# MultiSensor_MPL_TCA_0805.net
KiCad netlist of a schematic drawn in EAGLE
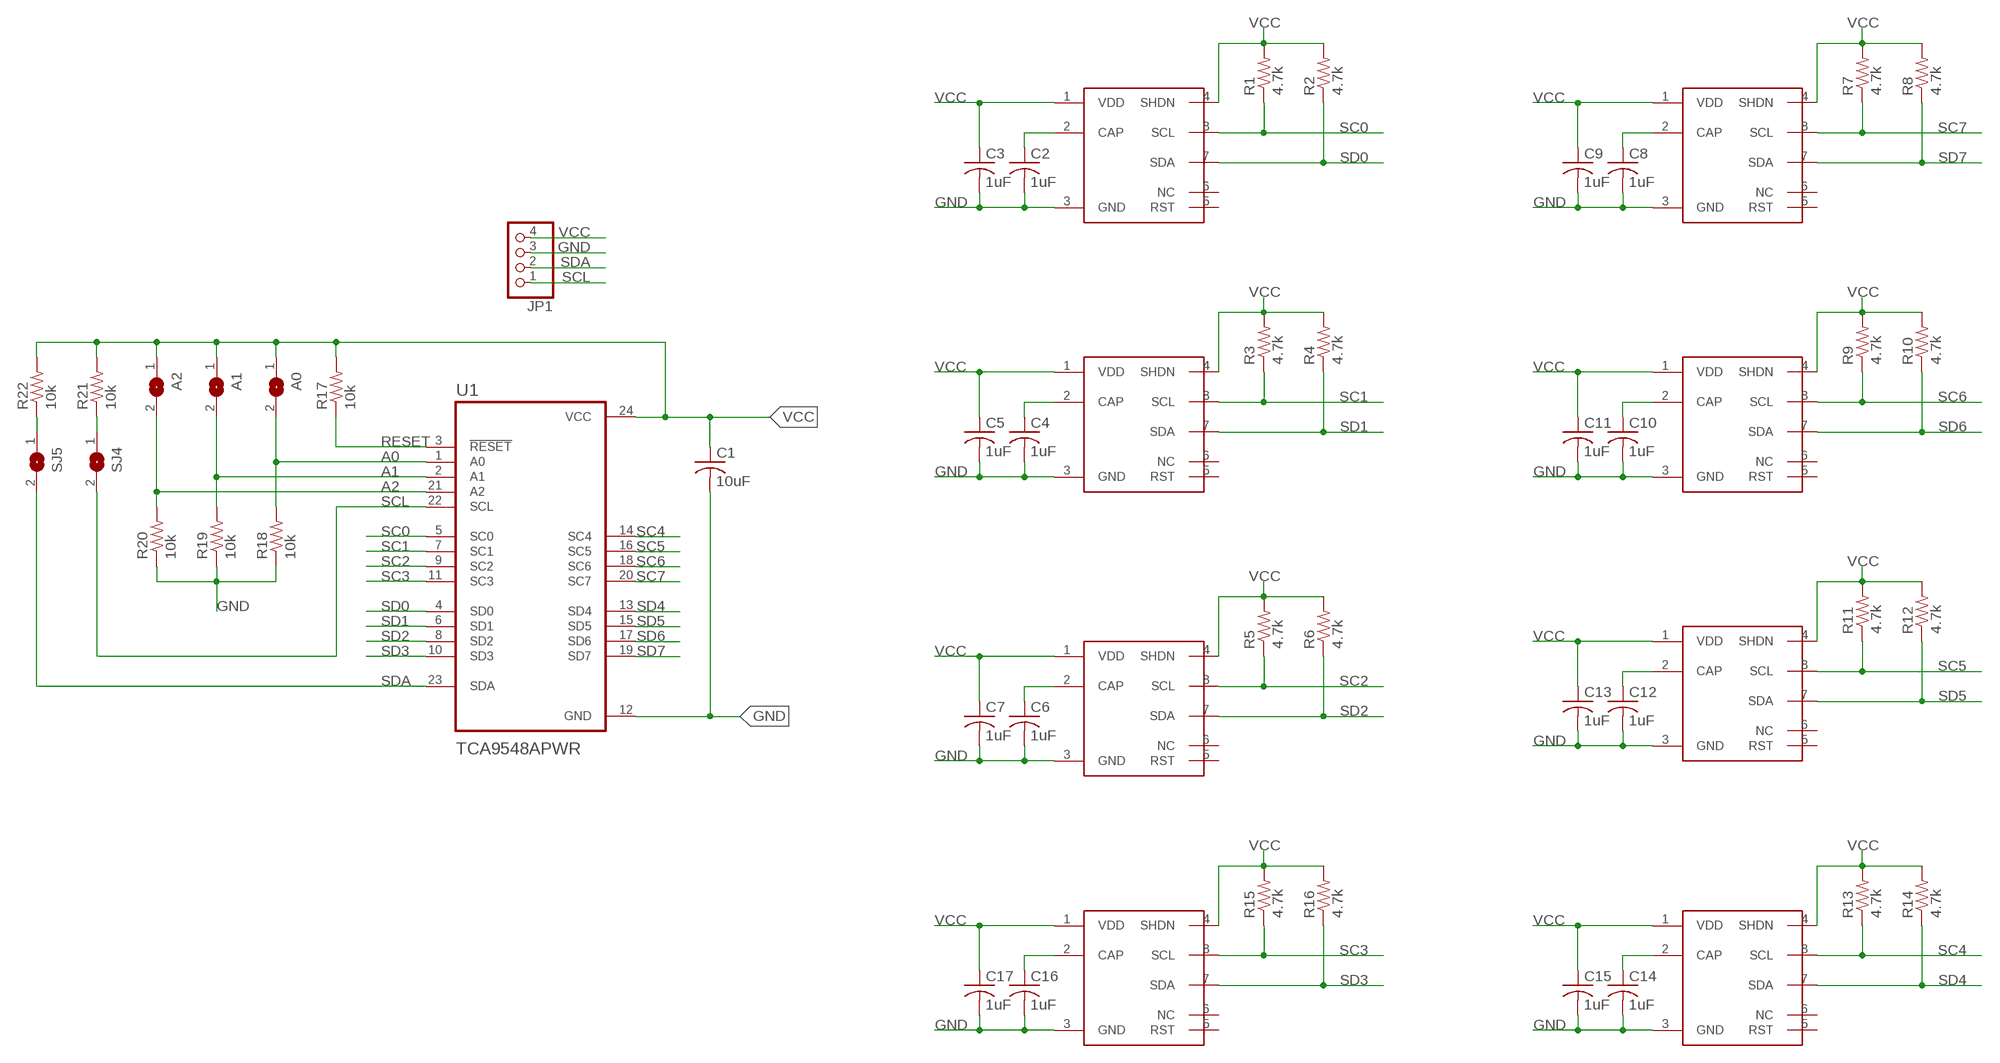
[diagram p0: schematic, sheet 1]

(export (version "E")
  (design (tool "Eeschema 10.0.6"))
  (components
    (comp (ref "A0") (value "SJ") (footprint "eagle-import:SJ") (libsource (lib "eagle-import") (part "SJ")))
    (comp (ref "A1") (value "SJ") (footprint "eagle-import:SJ") (libsource (lib "eagle-import") (part "SJ")))
    (comp (ref "A2") (value "SJ") (footprint "eagle-import:SJ") (libsource (lib "eagle-import") (part "SJ")))
    (comp (ref "B1")
      (value "MPL115A2T1")
      (footprint "eagle-import:MPL115A2T1")
      (libsource (lib "eagle-import") (part "MPL115A2T1"))
    )
    (comp (ref "B2")
      (value "MPL115A2T1")
      (footprint "eagle-import:MPL115A2T1")
      (libsource (lib "eagle-import") (part "MPL115A2T1"))
    )
    (comp (ref "B3")
      (value "MPL115A2T1")
      (footprint "eagle-import:MPL115A2T1")
      (libsource (lib "eagle-import") (part "MPL115A2T1"))
    )
    (comp (ref "B4")
      (value "MPL115A2T1")
      (footprint "eagle-import:MPL115A2T1")
      (libsource (lib "eagle-import") (part "MPL115A2T1"))
    )
    (comp (ref "B5")
      (value "MPL115A2T1")
      (footprint "eagle-import:MPL115A2T1")
      (libsource (lib "eagle-import") (part "MPL115A2T1"))
    )
    (comp (ref "B6")
      (value "MPL115A2T1")
      (footprint "eagle-import:MPL115A2T1")
      (libsource (lib "eagle-import") (part "MPL115A2T1"))
    )
    (comp (ref "B7")
      (value "MPL115A2T1")
      (footprint "eagle-import:MPL115A2T1")
      (libsource (lib "eagle-import") (part "MPL115A2T1"))
    )
    (comp (ref "B8")
      (value "MPL115A2T1")
      (footprint "eagle-import:MPL115A2T1")
      (libsource (lib "eagle-import") (part "MPL115A2T1"))
    )
    (comp (ref "C1")
      (value "10uF")
      (footprint "eagle-import:C1206")
      (libsource (lib "eagle-import") (part "C-USC1206"))
    )
    (comp (ref "C2")
      (value "1uF")
      (footprint "eagle-import:C0805")
      (libsource (lib "eagle-import") (part "C-USC0805"))
    )
    (comp (ref "C3")
      (value "1uF")
      (footprint "eagle-import:C0805")
      (libsource (lib "eagle-import") (part "C-USC0805"))
    )
    (comp (ref "C4")
      (value "1uF")
      (footprint "eagle-import:C0805")
      (libsource (lib "eagle-import") (part "C-USC0805"))
    )
    (comp (ref "C5")
      (value "1uF")
      (footprint "eagle-import:C0805")
      (libsource (lib "eagle-import") (part "C-USC0805"))
    )
    (comp (ref "C6")
      (value "1uF")
      (footprint "eagle-import:C0805")
      (libsource (lib "eagle-import") (part "C-USC0805"))
    )
    (comp (ref "C7")
      (value "1uF")
      (footprint "eagle-import:C0805")
      (libsource (lib "eagle-import") (part "C-USC0805"))
    )
    (comp (ref "C8")
      (value "1uF")
      (footprint "eagle-import:C0805")
      (libsource (lib "eagle-import") (part "C-USC0805"))
    )
    (comp (ref "C9")
      (value "1uF")
      (footprint "eagle-import:C0805")
      (libsource (lib "eagle-import") (part "C-USC0805"))
    )
    (comp (ref "C10")
      (value "1uF")
      (footprint "eagle-import:C0805")
      (libsource (lib "eagle-import") (part "C-USC0805"))
    )
    (comp (ref "C11")
      (value "1uF")
      (footprint "eagle-import:C0805")
      (libsource (lib "eagle-import") (part "C-USC0805"))
    )
    (comp (ref "C12")
      (value "1uF")
      (footprint "eagle-import:C0805")
      (libsource (lib "eagle-import") (part "C-USC0805"))
    )
    (comp (ref "C13")
      (value "1uF")
      (footprint "eagle-import:C0805")
      (libsource (lib "eagle-import") (part "C-USC0805"))
    )
    (comp (ref "C14")
      (value "1uF")
      (footprint "eagle-import:C0805")
      (libsource (lib "eagle-import") (part "C-USC0805"))
    )
    (comp (ref "C15")
      (value "1uF")
      (footprint "eagle-import:C0805")
      (libsource (lib "eagle-import") (part "C-USC0805"))
    )
    (comp (ref "C16")
      (value "1uF")
      (footprint "eagle-import:C0805")
      (libsource (lib "eagle-import") (part "C-USC0805"))
    )
    (comp (ref "C17")
      (value "1uF")
      (footprint "eagle-import:C0805")
      (libsource (lib "eagle-import") (part "C-USC0805"))
    )
    (comp (ref "JP1")
      (value "PINHD-1X4")
      (footprint "eagle-import:1X04")
      (libsource (lib "eagle-import") (part "PINHD-1X4"))
    )
    (comp (ref "R1")
      (value "4.7k")
      (footprint "eagle-import:R0805")
      (libsource (lib "eagle-import") (part "R-US_R0805"))
    )
    (comp (ref "R2")
      (value "4.7k")
      (footprint "eagle-import:R0805")
      (libsource (lib "eagle-import") (part "R-US_R0805"))
    )
    (comp (ref "R3")
      (value "4.7k")
      (footprint "eagle-import:R0805")
      (libsource (lib "eagle-import") (part "R-US_R0805"))
    )
    (comp (ref "R4")
      (value "4.7k")
      (footprint "eagle-import:R0805")
      (libsource (lib "eagle-import") (part "R-US_R0805"))
    )
    (comp (ref "R5")
      (value "4.7k")
      (footprint "eagle-import:R0805")
      (libsource (lib "eagle-import") (part "R-US_R0805"))
    )
    (comp (ref "R6")
      (value "4.7k")
      (footprint "eagle-import:R0805")
      (libsource (lib "eagle-import") (part "R-US_R0805"))
    )
    (comp (ref "R7")
      (value "4.7k")
      (footprint "eagle-import:R0805")
      (libsource (lib "eagle-import") (part "R-US_R0805"))
    )
    (comp (ref "R8")
      (value "4.7k")
      (footprint "eagle-import:R0805")
      (libsource (lib "eagle-import") (part "R-US_R0805"))
    )
    (comp (ref "R9")
      (value "4.7k")
      (footprint "eagle-import:R0805")
      (libsource (lib "eagle-import") (part "R-US_R0805"))
    )
    (comp (ref "R10")
      (value "4.7k")
      (footprint "eagle-import:R0805")
      (libsource (lib "eagle-import") (part "R-US_R0805"))
    )
    (comp (ref "R11")
      (value "4.7k")
      (footprint "eagle-import:R0805")
      (libsource (lib "eagle-import") (part "R-US_R0805"))
    )
    (comp (ref "R12")
      (value "4.7k")
      (footprint "eagle-import:R0805")
      (libsource (lib "eagle-import") (part "R-US_R0805"))
    )
    (comp (ref "R13")
      (value "4.7k")
      (footprint "eagle-import:R0805")
      (libsource (lib "eagle-import") (part "R-US_R0805"))
    )
    (comp (ref "R14")
      (value "4.7k")
      (footprint "eagle-import:R0805")
      (libsource (lib "eagle-import") (part "R-US_R0805"))
    )
    (comp (ref "R15")
      (value "4.7k")
      (footprint "eagle-import:R0805")
      (libsource (lib "eagle-import") (part "R-US_R0805"))
    )
    (comp (ref "R16")
      (value "4.7k")
      (footprint "eagle-import:R0805")
      (libsource (lib "eagle-import") (part "R-US_R0805"))
    )
    (comp (ref "R17")
      (value "10k")
      (footprint "eagle-import:R0805")
      (libsource (lib "eagle-import") (part "resistor_348_R-US_R0805"))
    )
    (comp (ref "R18")
      (value "10k")
      (footprint "eagle-import:R0805")
      (libsource (lib "eagle-import") (part "resistor_348_R-US_R0805"))
    )
    (comp (ref "R19")
      (value "10k")
      (footprint "eagle-import:R0805")
      (libsource (lib "eagle-import") (part "resistor_348_R-US_R0805"))
    )
    (comp (ref "R20")
      (value "10k")
      (footprint "eagle-import:R0805")
      (libsource (lib "eagle-import") (part "resistor_348_R-US_R0805"))
    )
    (comp (ref "R21")
      (value "10k")
      (footprint "eagle-import:R0805")
      (libsource (lib "eagle-import") (part "resistor_348_R-US_R0805"))
    )
    (comp (ref "R22")
      (value "10k")
      (footprint "eagle-import:R0805")
      (libsource (lib "eagle-import") (part "resistor_348_R-US_R0805"))
    )
    (comp (ref "SJ4") (value "SJ") (footprint "eagle-import:SJ") (libsource (lib "eagle-import") (part "SJ")))
    (comp (ref "SJ5") (value "SJ") (footprint "eagle-import:SJ") (libsource (lib "eagle-import") (part "SJ")))
    (comp (ref "U1")
      (value "TCA9548APWR")
      (footprint "eagle-import:SOP65P640X120-24N")
      (fields (field (name "DIGI-KEY_PART_NUMBER") "296-34905-1-ND") (field (name "MF") "Texas Instruments"))
      (libsource (lib "eagle-import") (part "TCA9548APWR"))
    )
  )
  (nets
    (net (code "1") (name "/A0") (class "Default")
      (node (ref "A0") (pin "2") (pinfunction "2_2") (pintype "passive"))
      (node (ref "R18") (pin "2") (pinfunction "2_2") (pintype "passive"))
      (node (ref "U1") (pin "1") (pinfunction "A0_1") (pintype "input"))
    )
    (net (code "2") (name "/A1") (class "Default")
      (node (ref "A1") (pin "2") (pinfunction "2_2") (pintype "passive"))
      (node (ref "R19") (pin "2") (pinfunction "2_2") (pintype "passive"))
      (node (ref "U1") (pin "2") (pinfunction "A1_2") (pintype "input"))
    )
    (net (code "3") (name "/A2") (class "Default")
      (node (ref "A2") (pin "2") (pinfunction "2_2") (pintype "passive"))
      (node (ref "R20") (pin "2") (pinfunction "2_2") (pintype "passive"))
      (node (ref "U1") (pin "21") (pinfunction "A2_21") (pintype "input"))
    )
    (net (code "4") (name "/RESET") (class "Default")
      (node (ref "R17") (pin "1") (pinfunction "1_1") (pintype "passive"))
      (node (ref "U1") (pin "3") (pinfunction "~{RESET}_3") (pintype "input"))
    )
    (net (code "5") (name "/SC0") (class "Default")
      (node (ref "B1") (pin "8") (pinfunction "SCL_8") (pintype "bidirectional"))
      (node (ref "R1") (pin "1") (pinfunction "1_1") (pintype "passive"))
      (node (ref "U1") (pin "5") (pinfunction "SC0_5") (pintype "bidirectional"))
    )
    (net (code "6") (name "/SC1") (class "Default")
      (node (ref "B2") (pin "8") (pinfunction "SCL_8") (pintype "bidirectional"))
      (node (ref "R3") (pin "1") (pinfunction "1_1") (pintype "passive"))
      (node (ref "U1") (pin "7") (pinfunction "SC1_7") (pintype "bidirectional"))
    )
    (net (code "7") (name "/SC2") (class "Default")
      (node (ref "B3") (pin "8") (pinfunction "SCL_8") (pintype "bidirectional"))
      (node (ref "R5") (pin "1") (pinfunction "1_1") (pintype "passive"))
      (node (ref "U1") (pin "9") (pinfunction "SC2_9") (pintype "bidirectional"))
    )
    (net (code "8") (name "/SC3") (class "Default")
      (node (ref "B8") (pin "8") (pinfunction "SCL_8") (pintype "bidirectional"))
      (node (ref "R15") (pin "1") (pinfunction "1_1") (pintype "passive"))
      (node (ref "U1") (pin "11") (pinfunction "SC3_11") (pintype "bidirectional"))
    )
    (net (code "9") (name "/SC4") (class "Default")
      (node (ref "B7") (pin "8") (pinfunction "SCL_8") (pintype "bidirectional"))
      (node (ref "R13") (pin "1") (pinfunction "1_1") (pintype "passive"))
      (node (ref "U1") (pin "14") (pinfunction "SC4_14") (pintype "bidirectional"))
    )
    (net (code "10") (name "/SC5") (class "Default")
      (node (ref "B6") (pin "8") (pinfunction "SCL_8") (pintype "bidirectional"))
      (node (ref "R11") (pin "1") (pinfunction "1_1") (pintype "passive"))
      (node (ref "U1") (pin "16") (pinfunction "SC5_16") (pintype "bidirectional"))
    )
    (net (code "11") (name "/SC6") (class "Default")
      (node (ref "B5") (pin "8") (pinfunction "SCL_8") (pintype "bidirectional"))
      (node (ref "R9") (pin "1") (pinfunction "1_1") (pintype "passive"))
      (node (ref "U1") (pin "18") (pinfunction "SC6_18") (pintype "bidirectional"))
    )
    (net (code "12") (name "/SC7") (class "Default")
      (node (ref "B4") (pin "8") (pinfunction "SCL_8") (pintype "bidirectional"))
      (node (ref "R7") (pin "1") (pinfunction "1_1") (pintype "passive"))
      (node (ref "U1") (pin "20") (pinfunction "SC7_20") (pintype "bidirectional"))
    )
    (net (code "13") (name "/SCL") (class "Default")
      (node (ref "JP1") (pin "1") (pinfunction "1_1") (pintype "passive"))
      (node (ref "SJ4") (pin "2") (pinfunction "2_2") (pintype "passive"))
      (node (ref "U1") (pin "22") (pinfunction "SCL_22") (pintype "input"))
    )
    (net (code "14") (name "/SD0") (class "Default")
      (node (ref "B1") (pin "7") (pinfunction "SDA_7") (pintype "bidirectional"))
      (node (ref "R2") (pin "1") (pinfunction "1_1") (pintype "passive"))
      (node (ref "U1") (pin "4") (pinfunction "SD0_4") (pintype "bidirectional"))
    )
    (net (code "15") (name "/SD1") (class "Default")
      (node (ref "B2") (pin "7") (pinfunction "SDA_7") (pintype "bidirectional"))
      (node (ref "R4") (pin "1") (pinfunction "1_1") (pintype "passive"))
      (node (ref "U1") (pin "6") (pinfunction "SD1_6") (pintype "bidirectional"))
    )
    (net (code "16") (name "/SD2") (class "Default")
      (node (ref "B3") (pin "7") (pinfunction "SDA_7") (pintype "bidirectional"))
      (node (ref "R6") (pin "1") (pinfunction "1_1") (pintype "passive"))
      (node (ref "U1") (pin "8") (pinfunction "SD2_8") (pintype "bidirectional"))
    )
    (net (code "17") (name "/SD3") (class "Default")
      (node (ref "B8") (pin "7") (pinfunction "SDA_7") (pintype "bidirectional"))
      (node (ref "R16") (pin "1") (pinfunction "1_1") (pintype "passive"))
      (node (ref "U1") (pin "10") (pinfunction "SD3_10") (pintype "bidirectional"))
    )
    (net (code "18") (name "/SD4") (class "Default")
      (node (ref "B7") (pin "7") (pinfunction "SDA_7") (pintype "bidirectional"))
      (node (ref "R14") (pin "1") (pinfunction "1_1") (pintype "passive"))
      (node (ref "U1") (pin "13") (pinfunction "SD4_13") (pintype "bidirectional"))
    )
    (net (code "19") (name "/SD5") (class "Default")
      (node (ref "B6") (pin "7") (pinfunction "SDA_7") (pintype "bidirectional"))
      (node (ref "R12") (pin "1") (pinfunction "1_1") (pintype "passive"))
      (node (ref "U1") (pin "15") (pinfunction "SD5_15") (pintype "bidirectional"))
    )
    (net (code "20") (name "/SD6") (class "Default")
      (node (ref "B5") (pin "7") (pinfunction "SDA_7") (pintype "bidirectional"))
      (node (ref "R10") (pin "1") (pinfunction "1_1") (pintype "passive"))
      (node (ref "U1") (pin "17") (pinfunction "SD6_17") (pintype "bidirectional"))
    )
    (net (code "21") (name "/SD7") (class "Default")
      (node (ref "B4") (pin "7") (pinfunction "SDA_7") (pintype "bidirectional"))
      (node (ref "R8") (pin "1") (pinfunction "1_1") (pintype "passive"))
      (node (ref "U1") (pin "19") (pinfunction "SD7_19") (pintype "bidirectional"))
    )
    (net (code "22") (name "/SDA") (class "Default")
      (node (ref "JP1") (pin "2") (pinfunction "2_2") (pintype "passive"))
      (node (ref "SJ5") (pin "2") (pinfunction "2_2") (pintype "passive"))
      (node (ref "U1") (pin "23") (pinfunction "SDA_23") (pintype "bidirectional"))
    )
    (net (code "23") (name "GND") (class "Default")
      (node (ref "B1") (pin "3") (pinfunction "GND_3") (pintype "bidirectional"))
      (node (ref "B2") (pin "3") (pinfunction "GND_3") (pintype "bidirectional"))
      (node (ref "B3") (pin "3") (pinfunction "GND_3") (pintype "bidirectional"))
      (node (ref "B4") (pin "3") (pinfunction "GND_3") (pintype "bidirectional"))
      (node (ref "B5") (pin "3") (pinfunction "GND_3") (pintype "bidirectional"))
      (node (ref "B6") (pin "3") (pinfunction "GND_3") (pintype "bidirectional"))
      (node (ref "B7") (pin "3") (pinfunction "GND_3") (pintype "bidirectional"))
      (node (ref "B8") (pin "3") (pinfunction "GND_3") (pintype "bidirectional"))
      (node (ref "C1") (pin "2") (pinfunction "2_2") (pintype "passive"))
      (node (ref "C10") (pin "2") (pinfunction "2_2") (pintype "passive"))
      (node (ref "C11") (pin "2") (pinfunction "2_2") (pintype "passive"))
      (node (ref "C12") (pin "2") (pinfunction "2_2") (pintype "passive"))
      (node (ref "C13") (pin "2") (pinfunction "2_2") (pintype "passive"))
      (node (ref "C14") (pin "2") (pinfunction "2_2") (pintype "passive"))
      (node (ref "C15") (pin "2") (pinfunction "2_2") (pintype "passive"))
      (node (ref "C16") (pin "2") (pinfunction "2_2") (pintype "passive"))
      (node (ref "C17") (pin "2") (pinfunction "2_2") (pintype "passive"))
      (node (ref "C2") (pin "2") (pinfunction "2_2") (pintype "passive"))
      (node (ref "C3") (pin "2") (pinfunction "2_2") (pintype "passive"))
      (node (ref "C4") (pin "2") (pinfunction "2_2") (pintype "passive"))
      (node (ref "C5") (pin "2") (pinfunction "2_2") (pintype "passive"))
      (node (ref "C6") (pin "2") (pinfunction "2_2") (pintype "passive"))
      (node (ref "C7") (pin "2") (pinfunction "2_2") (pintype "passive"))
      (node (ref "C8") (pin "2") (pinfunction "2_2") (pintype "passive"))
      (node (ref "C9") (pin "2") (pinfunction "2_2") (pintype "passive"))
      (node (ref "JP1") (pin "3") (pinfunction "3_3") (pintype "passive"))
      (node (ref "R18") (pin "1") (pinfunction "1_1") (pintype "passive"))
      (node (ref "R19") (pin "1") (pinfunction "1_1") (pintype "passive"))
      (node (ref "R20") (pin "1") (pinfunction "1_1") (pintype "passive"))
      (node (ref "U1") (pin "12") (pinfunction "GND_12") (pintype "power_in"))
    )
    (net (code "24") (name "Net-(B1-CAP)") (class "Default")
      (node (ref "B1") (pin "2") (pinfunction "CAP_2") (pintype "bidirectional"))
      (node (ref "C2") (pin "1") (pinfunction "1_1") (pintype "passive"))
    )
    (net (code "25") (name "Net-(B2-CAP)") (class "Default")
      (node (ref "B2") (pin "2") (pinfunction "CAP_2") (pintype "bidirectional"))
      (node (ref "C4") (pin "1") (pinfunction "1_1") (pintype "passive"))
    )
    (net (code "26") (name "Net-(B3-CAP)") (class "Default")
      (node (ref "B3") (pin "2") (pinfunction "CAP_2") (pintype "bidirectional"))
      (node (ref "C6") (pin "1") (pinfunction "1_1") (pintype "passive"))
    )
    (net (code "27") (name "Net-(B4-CAP)") (class "Default")
      (node (ref "B4") (pin "2") (pinfunction "CAP_2") (pintype "bidirectional"))
      (node (ref "C8") (pin "1") (pinfunction "1_1") (pintype "passive"))
    )
    (net (code "28") (name "Net-(B5-CAP)") (class "Default")
      (node (ref "B5") (pin "2") (pinfunction "CAP_2") (pintype "bidirectional"))
      (node (ref "C10") (pin "1") (pinfunction "1_1") (pintype "passive"))
    )
    (net (code "29") (name "Net-(B6-CAP)") (class "Default")
      (node (ref "B6") (pin "2") (pinfunction "CAP_2") (pintype "bidirectional"))
      (node (ref "C12") (pin "1") (pinfunction "1_1") (pintype "passive"))
    )
    (net (code "30") (name "Net-(B7-CAP)") (class "Default")
      (node (ref "B7") (pin "2") (pinfunction "CAP_2") (pintype "bidirectional"))
      (node (ref "C14") (pin "1") (pinfunction "1_1") (pintype "passive"))
    )
    (net (code "31") (name "Net-(B8-CAP)") (class "Default")
      (node (ref "B8") (pin "2") (pinfunction "CAP_2") (pintype "bidirectional"))
      (node (ref "C16") (pin "1") (pinfunction "1_1") (pintype "passive"))
    )
    (net (code "32") (name "Net-(R21-Pad1)") (class "Default")
      (node (ref "R21") (pin "1") (pinfunction "1_1") (pintype "passive"))
      (node (ref "SJ4") (pin "1") (pinfunction "1_1") (pintype "passive"))
    )
    (net (code "33") (name "Net-(R22-Pad1)") (class "Default")
      (node (ref "R22") (pin "1") (pinfunction "1_1") (pintype "passive"))
      (node (ref "SJ5") (pin "1") (pinfunction "1_1") (pintype "passive"))
    )
    (net (code "34") (name "VCC") (class "Default")
      (node (ref "A0") (pin "1") (pinfunction "1_1") (pintype "passive"))
      (node (ref "A1") (pin "1") (pinfunction "1_1") (pintype "passive"))
      (node (ref "A2") (pin "1") (pinfunction "1_1") (pintype "passive"))
      (node (ref "B1") (pin "1") (pinfunction "VDD_1") (pintype "bidirectional"))
      (node (ref "B1") (pin "4") (pinfunction "SHDN_4") (pintype "bidirectional"))
      (node (ref "B2") (pin "1") (pinfunction "VDD_1") (pintype "bidirectional"))
      (node (ref "B2") (pin "4") (pinfunction "SHDN_4") (pintype "bidirectional"))
      (node (ref "B3") (pin "1") (pinfunction "VDD_1") (pintype "bidirectional"))
      (node (ref "B3") (pin "4") (pinfunction "SHDN_4") (pintype "bidirectional"))
      (node (ref "B4") (pin "1") (pinfunction "VDD_1") (pintype "bidirectional"))
      (node (ref "B4") (pin "4") (pinfunction "SHDN_4") (pintype "bidirectional"))
      (node (ref "B5") (pin "1") (pinfunction "VDD_1") (pintype "bidirectional"))
      (node (ref "B5") (pin "4") (pinfunction "SHDN_4") (pintype "bidirectional"))
      (node (ref "B6") (pin "1") (pinfunction "VDD_1") (pintype "bidirectional"))
      (node (ref "B6") (pin "4") (pinfunction "SHDN_4") (pintype "bidirectional"))
      (node (ref "B7") (pin "1") (pinfunction "VDD_1") (pintype "bidirectional"))
      (node (ref "B7") (pin "4") (pinfunction "SHDN_4") (pintype "bidirectional"))
      (node (ref "B8") (pin "1") (pinfunction "VDD_1") (pintype "bidirectional"))
      (node (ref "B8") (pin "4") (pinfunction "SHDN_4") (pintype "bidirectional"))
      (node (ref "C1") (pin "1") (pinfunction "1_1") (pintype "passive"))
      (node (ref "C11") (pin "1") (pinfunction "1_1") (pintype "passive"))
      (node (ref "C13") (pin "1") (pinfunction "1_1") (pintype "passive"))
      (node (ref "C15") (pin "1") (pinfunction "1_1") (pintype "passive"))
      (node (ref "C17") (pin "1") (pinfunction "1_1") (pintype "passive"))
      (node (ref "C3") (pin "1") (pinfunction "1_1") (pintype "passive"))
      (node (ref "C5") (pin "1") (pinfunction "1_1") (pintype "passive"))
      (node (ref "C7") (pin "1") (pinfunction "1_1") (pintype "passive"))
      (node (ref "C9") (pin "1") (pinfunction "1_1") (pintype "passive"))
      (node (ref "JP1") (pin "4") (pinfunction "4_4") (pintype "passive"))
      (node (ref "R1") (pin "2") (pinfunction "2_2") (pintype "passive"))
      (node (ref "R10") (pin "2") (pinfunction "2_2") (pintype "passive"))
      (node (ref "R11") (pin "2") (pinfunction "2_2") (pintype "passive"))
      (node (ref "R12") (pin "2") (pinfunction "2_2") (pintype "passive"))
      (node (ref "R13") (pin "2") (pinfunction "2_2") (pintype "passive"))
      (node (ref "R14") (pin "2") (pinfunction "2_2") (pintype "passive"))
      (node (ref "R15") (pin "2") (pinfunction "2_2") (pintype "passive"))
      (node (ref "R16") (pin "2") (pinfunction "2_2") (pintype "passive"))
      (node (ref "R17") (pin "2") (pinfunction "2_2") (pintype "passive"))
      (node (ref "R2") (pin "2") (pinfunction "2_2") (pintype "passive"))
      (node (ref "R21") (pin "2") (pinfunction "2_2") (pintype "passive"))
      (node (ref "R22") (pin "2") (pinfunction "2_2") (pintype "passive"))
      (node (ref "R3") (pin "2") (pinfunction "2_2") (pintype "passive"))
      (node (ref "R4") (pin "2") (pinfunction "2_2") (pintype "passive"))
      (node (ref "R5") (pin "2") (pinfunction "2_2") (pintype "passive"))
      (node (ref "R6") (pin "2") (pinfunction "2_2") (pintype "passive"))
      (node (ref "R7") (pin "2") (pinfunction "2_2") (pintype "passive"))
      (node (ref "R8") (pin "2") (pinfunction "2_2") (pintype "passive"))
      (node (ref "R9") (pin "2") (pinfunction "2_2") (pintype "passive"))
      (node (ref "U1") (pin "24") (pinfunction "VCC_24") (pintype "power_in"))
    )
    (net (code "35") (name "unconnected-(B1-NC-Pad6)") (class "Default")
      (node (ref "B1") (pin "6") (pinfunction "NC_6") (pintype "bidirectional"))
    )
    (net (code "36") (name "unconnected-(B1-RST-Pad5)") (class "Default")
      (node (ref "B1") (pin "5") (pinfunction "RST_5") (pintype "bidirectional"))
    )
    (net (code "37") (name "unconnected-(B2-NC-Pad6)") (class "Default")
      (node (ref "B2") (pin "6") (pinfunction "NC_6") (pintype "bidirectional"))
    )
    (net (code "38") (name "unconnected-(B2-RST-Pad5)") (class "Default")
      (node (ref "B2") (pin "5") (pinfunction "RST_5") (pintype "bidirectional"))
    )
    (net (code "39") (name "unconnected-(B3-NC-Pad6)") (class "Default")
      (node (ref "B3") (pin "6") (pinfunction "NC_6") (pintype "bidirectional"))
    )
    (net (code "40") (name "unconnected-(B3-RST-Pad5)") (class "Default")
      (node (ref "B3") (pin "5") (pinfunction "RST_5") (pintype "bidirectional"))
    )
    (net (code "41") (name "unconnected-(B4-NC-Pad6)") (class "Default")
      (node (ref "B4") (pin "6") (pinfunction "NC_6") (pintype "bidirectional"))
    )
    (net (code "42") (name "unconnected-(B4-RST-Pad5)") (class "Default")
      (node (ref "B4") (pin "5") (pinfunction "RST_5") (pintype "bidirectional"))
    )
    (net (code "43") (name "unconnected-(B5-NC-Pad6)") (class "Default")
      (node (ref "B5") (pin "6") (pinfunction "NC_6") (pintype "bidirectional"))
    )
    (net (code "44") (name "unconnected-(B5-RST-Pad5)") (class "Default")
      (node (ref "B5") (pin "5") (pinfunction "RST_5") (pintype "bidirectional"))
    )
    (net (code "45") (name "unconnected-(B6-NC-Pad6)") (class "Default")
      (node (ref "B6") (pin "6") (pinfunction "NC_6") (pintype "bidirectional"))
    )
    (net (code "46") (name "unconnected-(B6-RST-Pad5)") (class "Default")
      (node (ref "B6") (pin "5") (pinfunction "RST_5") (pintype "bidirectional"))
    )
    (net (code "47") (name "unconnected-(B7-NC-Pad6)") (class "Default")
      (node (ref "B7") (pin "6") (pinfunction "NC_6") (pintype "bidirectional"))
    )
    (net (code "48") (name "unconnected-(B7-RST-Pad5)") (class "Default")
      (node (ref "B7") (pin "5") (pinfunction "RST_5") (pintype "bidirectional"))
    )
    (net (code "49") (name "unconnected-(B8-NC-Pad6)") (class "Default")
      (node (ref "B8") (pin "6") (pinfunction "NC_6") (pintype "bidirectional"))
    )
    (net (code "50") (name "unconnected-(B8-RST-Pad5)") (class "Default")
      (node (ref "B8") (pin "5") (pinfunction "RST_5") (pintype "bidirectional"))
    )
  )
)
